# ADC_8CH.net
KiCad netlist of a schematic drawn in Altium Designer
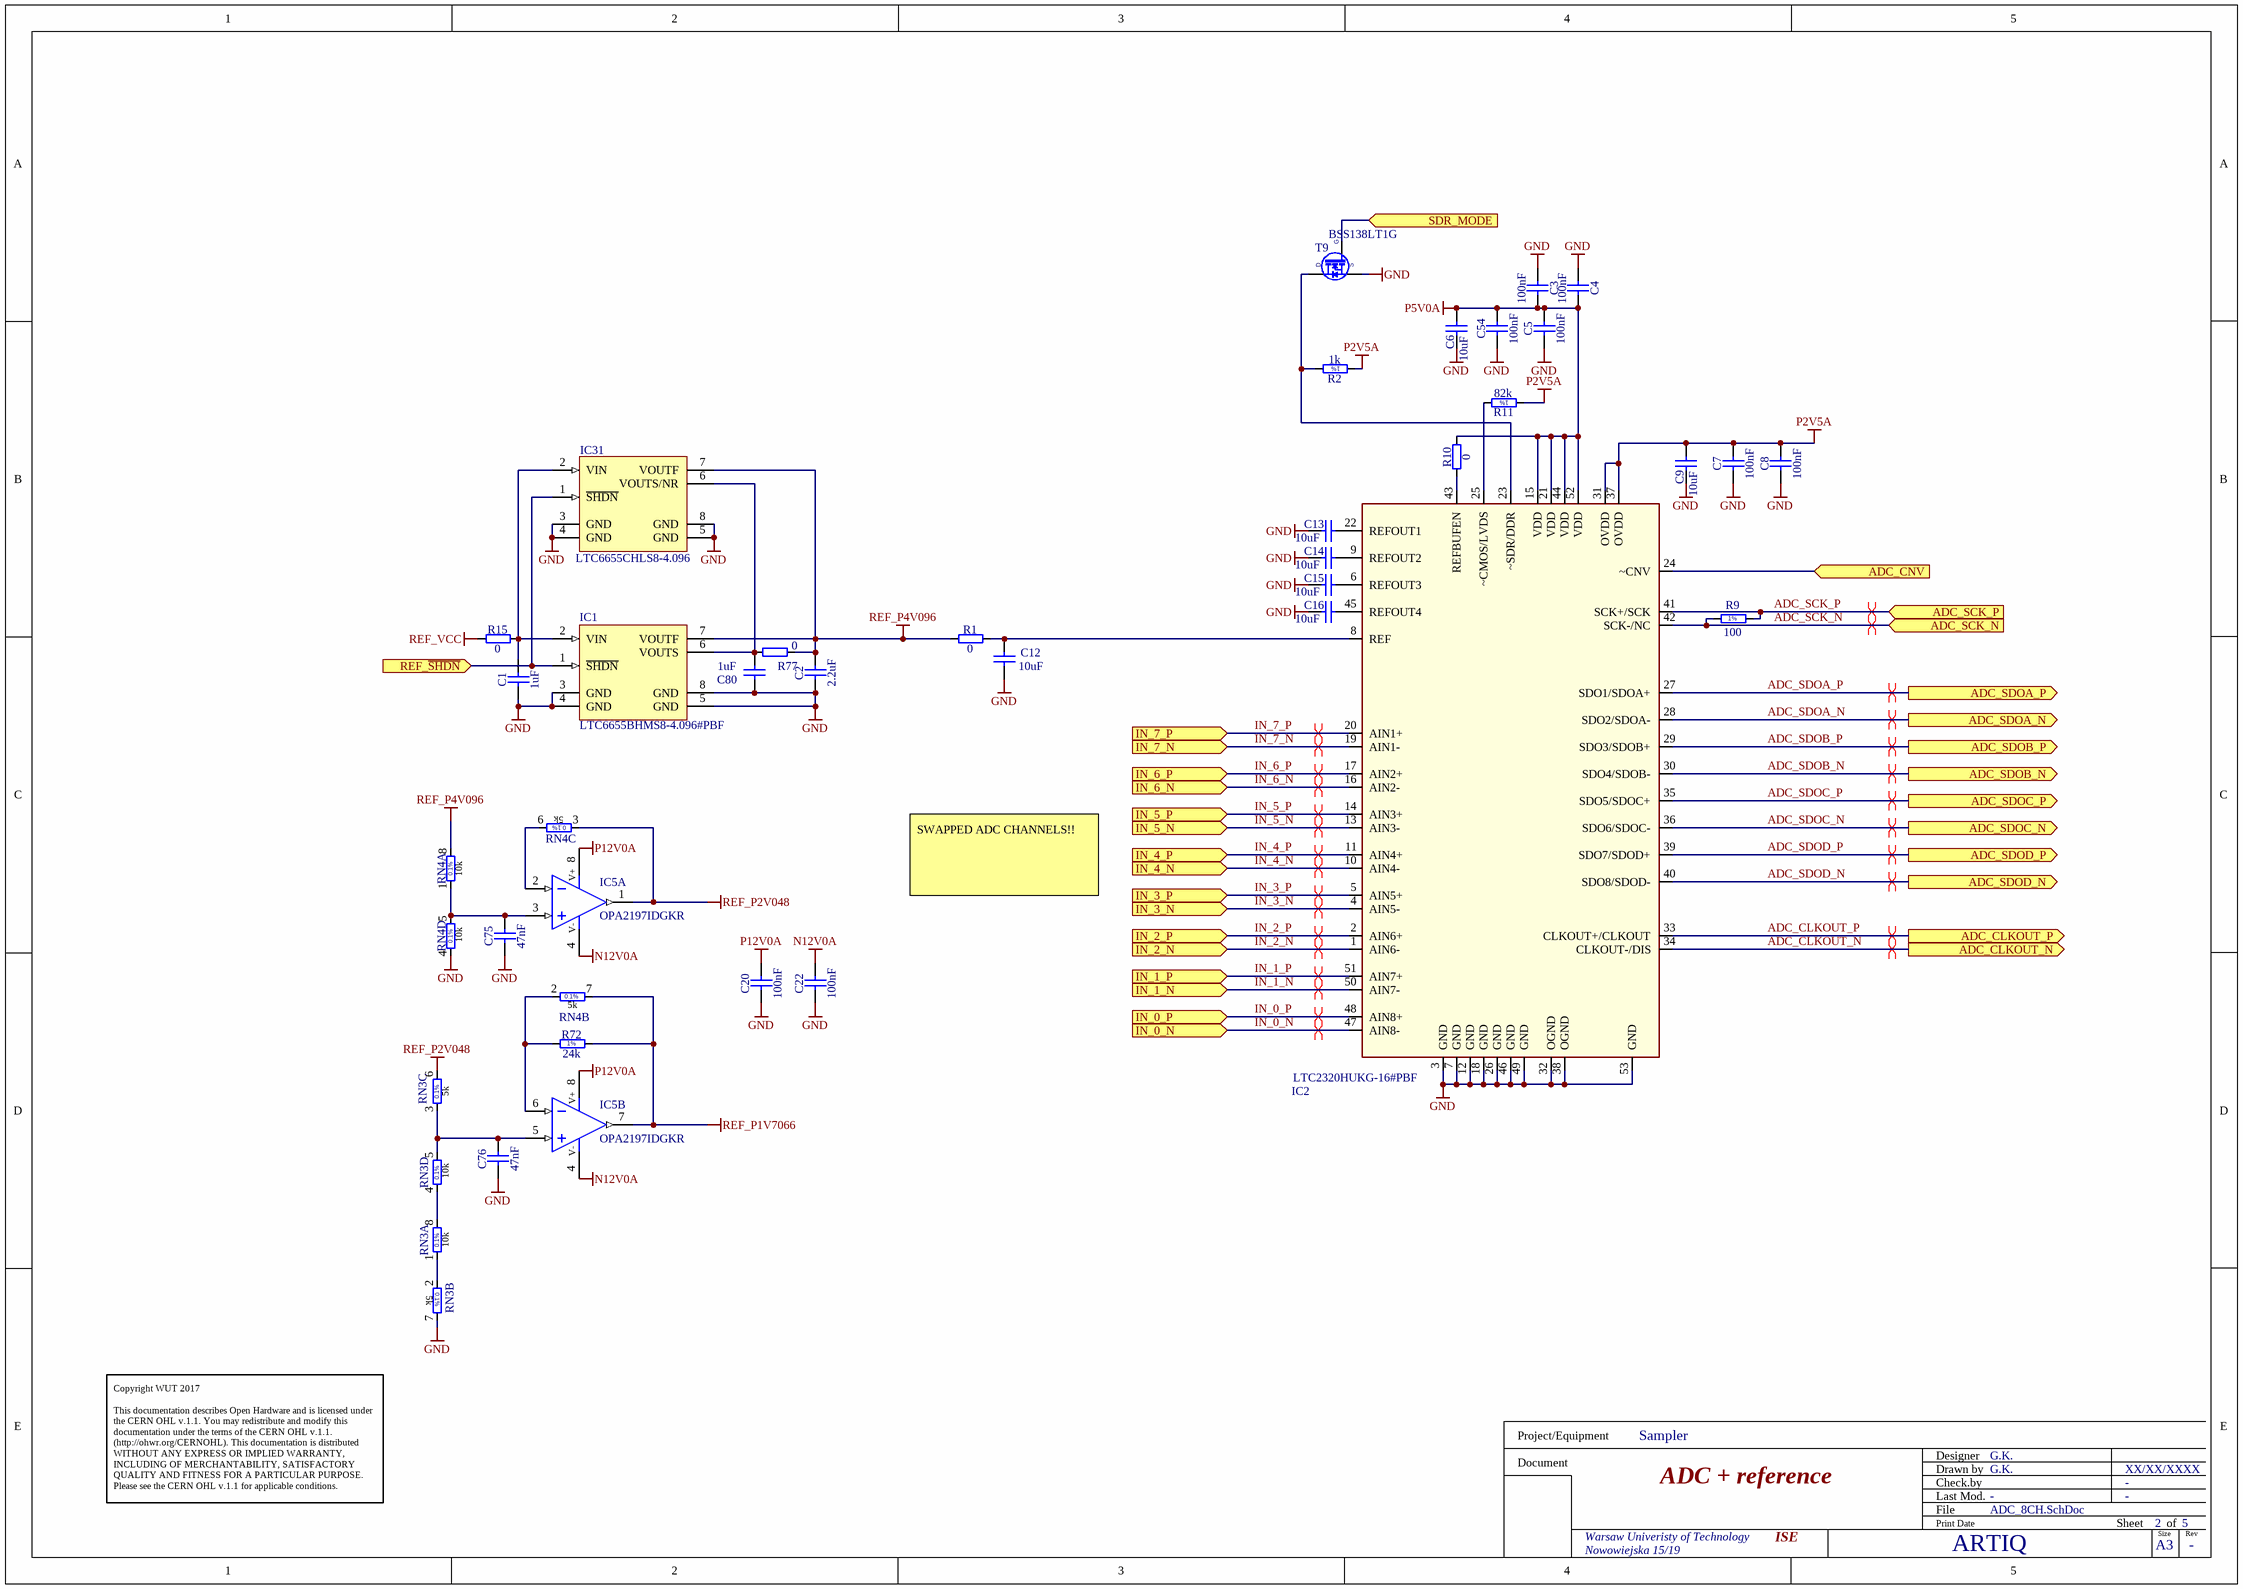
[diagram p0: ADC_8CH.SchDoc]

(export (version "E")
  (design (tool "Eeschema 10.0.6"))
  (components
    (comp (ref "C1")
      (value "1uF")
      (footprint "CAPC1608X87N")
      (description "Non-polarised capacitor")
      (fields
        (field (name "PART NUMBER") "CC0603_1UF_25V_10%_X7R")
        (field (name "VOLTAGE") "25V")
        (field (name "AUTHOR") "CERN DEM JLC")
      )
      (libsource (lib "Capacitors") (part "Capacitor - non polarized"))
    )
    (comp (ref "C2")
      (value "2.2uF")
      (footprint "CAPC1608X87N")
      (description "Non-polarised capacitor")
      (fields
        (field (name "PART NUMBER") "CC0603_2.2UF_16V_10%_X5R")
        (field (name "VOLTAGE") "16V")
        (field (name "AUTHOR") "CERN DEM JLC")
      )
      (libsource (lib "Capacitors") (part "Capacitor - non polarized"))
    )
    (comp (ref "C3")
      (value "100nF")
      (footprint "CAPC1608X87N")
      (description "Non-polarised capacitor")
      (fields
        (field (name "PART NUMBER") "CC0603_100NF_50V_10%_X7R")
        (field (name "VOLTAGE") "50V")
        (field (name "AUTHOR") "CERN DEM JLC")
      )
      (libsource (lib "Capacitors") (part "Capacitor - non polarized"))
    )
    (comp (ref "C4")
      (value "100nF")
      (footprint "CAPC1608X87N")
      (description "Non-polarised capacitor")
      (fields
        (field (name "PART NUMBER") "CC0603_100NF_50V_10%_X7R")
        (field (name "VOLTAGE") "50V")
        (field (name "AUTHOR") "CERN DEM JLC")
      )
      (libsource (lib "Capacitors") (part "Capacitor - non polarized"))
    )
    (comp (ref "C5")
      (value "100nF")
      (footprint "CAPC1608X87N")
      (description "Non-polarised capacitor")
      (fields
        (field (name "PART NUMBER") "CC0603_100NF_50V_10%_X7R")
        (field (name "VOLTAGE") "50V")
        (field (name "AUTHOR") "CERN DEM JLC")
      )
      (libsource (lib "Capacitors") (part "Capacitor - non polarized"))
    )
    (comp (ref "C6")
      (value "10uF")
      (footprint "CAPC2012X95N")
      (description "Non-polarised capacitor")
      (fields
        (field (name "PART NUMBER") "CC0805_10UF_25V_10%_X5R")
        (field (name "VOLTAGE") "25V")
        (field (name "AUTHOR") "CERN DEM JLC")
      )
      (libsource (lib "Capacitors") (part "Capacitor - non polarized"))
    )
    (comp (ref "C7")
      (value "100nF")
      (footprint "CAPC1608X87N")
      (description "Non-polarised capacitor")
      (fields
        (field (name "PART NUMBER") "CC0603_100NF_50V_10%_X7R")
        (field (name "VOLTAGE") "50V")
        (field (name "AUTHOR") "CERN DEM JLC")
      )
      (libsource (lib "Capacitors") (part "Capacitor - non polarized"))
    )
    (comp (ref "C8")
      (value "100nF")
      (footprint "CAPC1608X87N")
      (description "Non-polarised capacitor")
      (fields
        (field (name "PART NUMBER") "CC0603_100NF_50V_10%_X7R")
        (field (name "VOLTAGE") "50V")
        (field (name "AUTHOR") "CERN DEM JLC")
      )
      (libsource (lib "Capacitors") (part "Capacitor - non polarized"))
    )
    (comp (ref "C9")
      (value "10uF")
      (footprint "CAPC2012X95N")
      (description "Non-polarised capacitor")
      (fields
        (field (name "PART NUMBER") "CC0805_10UF_25V_10%_X5R")
        (field (name "VOLTAGE") "25V")
        (field (name "AUTHOR") "CERN DEM JLC")
      )
      (libsource (lib "Capacitors") (part "Capacitor - non polarized"))
    )
    (comp (ref "C12")
      (value "10uF")
      (footprint "CAPC2012X95N")
      (description "Non-polarised capacitor")
      (fields
        (field (name "PART NUMBER") "CC0805_10UF_25V_10%_X5R")
        (field (name "VOLTAGE") "25V")
        (field (name "AUTHOR") "CERN DEM JLC")
      )
      (libsource (lib "Capacitors") (part "Capacitor - non polarized"))
    )
    (comp (ref "C13")
      (value "10uF")
      (footprint "CAPC2012X95N")
      (description "Non-polarised capacitor")
      (fields
        (field (name "PART NUMBER") "CC0805_10UF_25V_10%_X5R")
        (field (name "VOLTAGE") "25V")
        (field (name "AUTHOR") "CERN DEM JLC")
      )
      (libsource (lib "Capacitors") (part "Capacitor - non polarized"))
    )
    (comp (ref "C14")
      (value "10uF")
      (footprint "CAPC2012X95N")
      (description "Non-polarised capacitor")
      (fields
        (field (name "PART NUMBER") "CC0805_10UF_25V_10%_X5R")
        (field (name "VOLTAGE") "25V")
        (field (name "AUTHOR") "CERN DEM JLC")
      )
      (libsource (lib "Capacitors") (part "Capacitor - non polarized"))
    )
    (comp (ref "C15")
      (value "10uF")
      (footprint "CAPC2012X95N")
      (description "Non-polarised capacitor")
      (fields
        (field (name "PART NUMBER") "CC0805_10UF_25V_10%_X5R")
        (field (name "VOLTAGE") "25V")
        (field (name "AUTHOR") "CERN DEM JLC")
      )
      (libsource (lib "Capacitors") (part "Capacitor - non polarized"))
    )
    (comp (ref "C16")
      (value "10uF")
      (footprint "CAPC2012X95N")
      (description "Non-polarised capacitor")
      (fields
        (field (name "PART NUMBER") "CC0805_10UF_25V_10%_X5R")
        (field (name "VOLTAGE") "25V")
        (field (name "AUTHOR") "CERN DEM JLC")
      )
      (libsource (lib "Capacitors") (part "Capacitor - non polarized"))
    )
    (comp (ref "C20")
      (value "100nF")
      (footprint "CAPC1005X55N")
      (description "Non-polarised capacitor")
      (fields
        (field (name "PART NUMBER") "CC0402_100NF_16V_10%_X5R")
        (field (name "VOLTAGE") "16V")
        (field (name "AUTHOR") "CERN DEM JLC")
      )
      (libsource (lib "Capacitors") (part "Capacitor - non polarized"))
    )
    (comp (ref "C22")
      (value "100nF")
      (footprint "CAPC1005X55N")
      (description "Non-polarised capacitor")
      (fields
        (field (name "PART NUMBER") "CC0402_100NF_16V_10%_X5R")
        (field (name "VOLTAGE") "16V")
        (field (name "AUTHOR") "CERN DEM JLC")
      )
      (libsource (lib "Capacitors") (part "Capacitor - non polarized"))
    )
    (comp (ref "C54")
      (value "100nF")
      (footprint "CAPC1608X87N")
      (description "Non-polarised capacitor")
      (fields
        (field (name "PART NUMBER") "CC0603_100NF_50V_10%_X7R")
        (field (name "VOLTAGE") "50V")
        (field (name "AUTHOR") "CERN DEM JLC")
      )
      (libsource (lib "Capacitors") (part "Capacitor - non polarized"))
    )
    (comp (ref "C75")
      (value "47nF")
      (footprint "CAPC2012X135N")
      (description "Non-polarised capacitor")
      (fields
        (field (name "PART NUMBER") "CC0805_47NF_25V_5%_C0G")
        (field (name "VOLTAGE") "25V")
        (field (name "AUTHOR") "CERN DEM JLC")
      )
      (libsource (lib "Capacitors") (part "Capacitor - non polarized"))
    )
    (comp (ref "C76")
      (value "47nF")
      (footprint "CAPC2012X135N")
      (description "Non-polarised capacitor")
      (fields
        (field (name "PART NUMBER") "CC0805_47NF_25V_5%_C0G")
        (field (name "VOLTAGE") "25V")
        (field (name "AUTHOR") "CERN DEM JLC")
      )
      (libsource (lib "Capacitors") (part "Capacitor - non polarized"))
    )
    (comp (ref "C80")
      (value "1uF")
      (footprint "CAPC1608X87N")
      (description "Non-polarised capacitor")
      (fields
        (field (name "PART NUMBER") "CC0603_1UF_25V_10%_X7R")
        (field (name "VOLTAGE") "25V")
        (field (name "AUTHOR") "CERN DEM JLC")
      )
      (libsource (lib "Capacitors") (part "Capacitor - non polarized"))
    )
    (comp (ref "IC1")
      (value "LTC6655BHMS8-4.096#PBF")
      (footprint "SOP65P490X110-8N")
      (description "0.25ppm Noise, Low Drift Precision Buffered Voltage Reference")
      (fields (field (name "MANUFACTURER") "LINEAR TECHNOLOGY") (field (name "AUTHOR") "GK"))
      (libsource (lib "LIBRARY_SCH") (part "REF_LTC6655"))
    )
    (comp (ref "IC2")
      (value "LTC2320HUKG-16#PBF")
      (footprint "QFN50P700X800X80_HS-53M")
      (description "Octal, 16-Bit, 1.5Msps/Ch  Simultaneous Sampling ADC")
      (fields (field (name "MANUFACTURER") "LINEAR TECHNOLOGY") (field (name "AUTHOR") "GK"))
      (libsource (lib "LIBRARY_SCH") (part "ADC_LTC2320HUKG-16"))
    )
    (comp (ref "IC5")
      (value "OPA2197IDGKR")
      (footprint "SOP65P490X110-8N")
      (description "36-V, Precision, Rail-to-Rail Input Output, Low Offset Voltage Op Amp 8-VSSOP")
      (fields (field (name "MANUFACTURER") "TEXAS INSTRUMENTS") (field (name "AUTHOR") "GK"))
      (libsource (lib "LIBRARY_SCH") (part "OA_OPA2197IDGKR"))
    )
    (comp (ref "IC31")
      (value "LTC6655CHLS8-4.096")
      (footprint "LCCS127P500X500X145-8N")
      (description "4.096, 1uA Precision Voltage Reference")
      (fields
        (field (name "PART NUMBER") "LTC6655CHLS8-4.096#PBF")
        (field (name "MANUFACTURER") "LINEAR TECHNOLOGY")
        (field (name "AUTHOR") "GK")
      )
      (libsource (lib "ICs_Analog_Interfaces") (part "REF_LTC6655CHLS8-4.096"))
    )
    (comp (ref "R1")
      (value "0")
      (footprint "RESC1005X40N")
      (description "Resistor")
      (fields
        (field (name "PART NUMBER") "R0402_0R_JUMPER")
        (field (name "MANUFACTURER") "GENERIC")
        (field (name "AUTHOR") "CERN DEM JLC")
      )
      (libsource (lib "Resistors") (part "Resistor"))
    )
    (comp (ref "R2")
      (value "1k")
      (footprint "RESC1608X55N")
      (description "Resistor - 1%")
      (fields
        (field (name "PART NUMBER") "R0603_1K_1%_0.1W_100PPM")
        (field (name "POWER") "0.1W")
        (field (name "AUTHOR") "CERN DEM JLC")
      )
      (libsource (lib "Resistors") (part "Resistor - 1%"))
    )
    (comp (ref "R9")
      (value "100")
      (footprint "RESC1005X40N")
      (description "Resistor - 1%")
      (fields
        (field (name "PART NUMBER") "R0402_100R_1%_0.1W_100PPM")
        (field (name "POWER") "0.1W")
        (field (name "AUTHOR") "CERN DEM JLC")
      )
      (libsource (lib "Resistors") (part "Resistor - 1%"))
    )
    (comp (ref "R10")
      (value "0")
      (footprint "RESC1005X40N")
      (description "Resistor")
      (fields
        (field (name "PART NUMBER") "R0402_0R_JUMPER")
        (field (name "MANUFACTURER") "GENERIC")
        (field (name "AUTHOR") "CERN DEM JLC")
      )
      (libsource (lib "Resistors") (part "Resistor"))
    )
    (comp (ref "R11")
      (value "82k")
      (footprint "RESC1608X55N")
      (description "Resistor - 1%")
      (fields
        (field (name "PART NUMBER") "R0603_82K_1%_0.1W_100PPM")
        (field (name "POWER") "0.1W")
        (field (name "AUTHOR") "CERN DEM JLC")
      )
      (libsource (lib "Resistors") (part "Resistor - 1%"))
    )
    (comp (ref "R15")
      (value "0")
      (footprint "RESC1005X40N")
      (description "Resistor")
      (fields
        (field (name "PART NUMBER") "R0402_0R_JUMPER")
        (field (name "MANUFACTURER") "GENERIC")
        (field (name "AUTHOR") "CERN DEM JLC")
      )
      (libsource (lib "Resistors") (part "Resistor"))
    )
    (comp (ref "R72")
      (value "24k")
      (footprint "RESC1608X55N")
      (description "Resistor - 1%")
      (fields
        (field (name "PART NUMBER") "R0603_24K_1%_0.1W_100PPM")
        (field (name "POWER") "0.1W")
        (field (name "AUTHOR") "CERN DEM JLC")
      )
      (libsource (lib "Resistors") (part "Resistor - 1%"))
    )
    (comp (ref "R77")
      (value "0")
      (footprint "RESC1005X40N")
      (description "Resistor")
      (fields
        (field (name "PART NUMBER") "R0402_0R_JUMPER")
        (field (name "MANUFACTURER") "GENERIC")
        (field (name "AUTHOR") "CERN DEM JLC")
      )
      (libsource (lib "Resistors") (part "Resistor"))
    )
    (comp (ref "RN3")
      (value "10k 5K 5K 10K")
      (footprint "SOIC127P600X175-8N")
      (description "DIL8 Resistor Network 4 Resistors 10k-5k-5k-10k 0.1%")
      (fields
        (field (name "PART NUMBER") "RN_10K_5K_VISHAY_AORN2-1AT3")
        (field (name "POWER") "4x0.1W")
        (field (name "AUTHOR") "CERN DEM JLC")
      )
      (libsource (lib "Resistors") (part "RN DIL8_4xR_10k-5k-5k-10k_0.1%"))
    )
    (comp (ref "RN4")
      (value "10k 5K 5K 10K")
      (footprint "SOIC127P600X175-8N")
      (description "DIL8 Resistor Network 4 Resistors 10k-5k-5k-10k 0.1%")
      (fields
        (field (name "PART NUMBER") "RN_10K_5K_VISHAY_AORN2-1AT3")
        (field (name "POWER") "4x0.1W")
        (field (name "AUTHOR") "CERN DEM JLC")
      )
      (libsource (lib "Resistors") (part "RN DIL8_4xR_10k-5k-5k-10k_0.1%"))
    )
    (comp (ref "T9")
      (value "BSS138LT1G")
      (footprint "SOT95P240X110-3N")
      (description "N-CHANNEL MOSFET WITH DIODE")
      (fields (field (name "MANUFACTURER") "ON SEMICONDUCTOR") (field (name "AUTHOR") "CERN DEM JLC"))
      (libsource (lib "ICs And Semiconductors") (part "N-MOSFET-D 1G 2S 3D"))
    )
  )
  (nets
    (net (code "1") (name "/ADC_CLKOUT_N") (class "Default")
      (node (ref "IC2") (pin "34") (pinfunction "CLKOUT-/DIS_34") (pintype "passive"))
    )
    (net (code "2") (name "/ADC_CLKOUT_P") (class "Default")
      (node (ref "IC2") (pin "33") (pinfunction "CLKOUT+/CLKOUT_33") (pintype "passive"))
    )
    (net (code "3") (name "/ADC_CNV") (class "Default")
      (node (ref "IC2") (pin "24") (pinfunction "~CNV_24") (pintype "passive"))
    )
    (net (code "4") (name "/ADC_SCK_N") (class "Default")
      (node (ref "IC2") (pin "42") (pinfunction "SCK-/NC_42") (pintype "passive"))
      (node (ref "R9") (pin "1") (pinfunction "1_1") (pintype "passive"))
    )
    (net (code "5") (name "/ADC_SCK_P") (class "Default")
      (node (ref "IC2") (pin "41") (pinfunction "SCK+/SCK_41") (pintype "passive"))
      (node (ref "R9") (pin "2") (pinfunction "2_2") (pintype "passive"))
    )
    (net (code "6") (name "/ADC_SDOA_N") (class "Default")
      (node (ref "IC2") (pin "28") (pinfunction "SDO2/SDOA-_28") (pintype "passive"))
    )
    (net (code "7") (name "/ADC_SDOA_P") (class "Default")
      (node (ref "IC2") (pin "27") (pinfunction "SDO1/SDOA+_27") (pintype "passive"))
    )
    (net (code "8") (name "/ADC_SDOB_N") (class "Default")
      (node (ref "IC2") (pin "30") (pinfunction "SDO4/SDOB-_30") (pintype "passive"))
    )
    (net (code "9") (name "/ADC_SDOB_P") (class "Default")
      (node (ref "IC2") (pin "29") (pinfunction "SDO3/SDOB+_29") (pintype "passive"))
    )
    (net (code "10") (name "/ADC_SDOC_N") (class "Default")
      (node (ref "IC2") (pin "36") (pinfunction "SDO6/SDOC-_36") (pintype "passive"))
    )
    (net (code "11") (name "/ADC_SDOC_P") (class "Default")
      (node (ref "IC2") (pin "35") (pinfunction "SDO5/SDOC+_35") (pintype "passive"))
    )
    (net (code "12") (name "/ADC_SDOD_N") (class "Default")
      (node (ref "IC2") (pin "40") (pinfunction "SDO8/SDOD-_40") (pintype "passive"))
    )
    (net (code "13") (name "/ADC_SDOD_P") (class "Default")
      (node (ref "IC2") (pin "39") (pinfunction "SDO7/SDOD+_39") (pintype "passive"))
    )
    (net (code "14") (name "/IN_0_N") (class "Default")
      (node (ref "IC2") (pin "47") (pinfunction "AIN8-_47") (pintype "passive"))
    )
    (net (code "15") (name "/IN_0_P") (class "Default")
      (node (ref "IC2") (pin "48") (pinfunction "AIN8+_48") (pintype "passive"))
    )
    (net (code "16") (name "/IN_1_N") (class "Default")
      (node (ref "IC2") (pin "50") (pinfunction "AIN7-_50") (pintype "passive"))
    )
    (net (code "17") (name "/IN_1_P") (class "Default")
      (node (ref "IC2") (pin "51") (pinfunction "AIN7+_51") (pintype "passive"))
    )
    (net (code "18") (name "/IN_2_N") (class "Default")
      (node (ref "IC2") (pin "1") (pinfunction "AIN6-_1") (pintype "passive"))
    )
    (net (code "19") (name "/IN_2_P") (class "Default")
      (node (ref "IC2") (pin "2") (pinfunction "AIN6+_2") (pintype "passive"))
    )
    (net (code "20") (name "/IN_3_N") (class "Default")
      (node (ref "IC2") (pin "4") (pinfunction "AIN5-_4") (pintype "passive"))
    )
    (net (code "21") (name "/IN_3_P") (class "Default")
      (node (ref "IC2") (pin "5") (pinfunction "AIN5+_5") (pintype "passive"))
    )
    (net (code "22") (name "/IN_4_N") (class "Default")
      (node (ref "IC2") (pin "10") (pinfunction "AIN4-_10") (pintype "passive"))
    )
    (net (code "23") (name "/IN_4_P") (class "Default")
      (node (ref "IC2") (pin "11") (pinfunction "AIN4+_11") (pintype "passive"))
    )
    (net (code "24") (name "/IN_5_N") (class "Default")
      (node (ref "IC2") (pin "13") (pinfunction "AIN3-_13") (pintype "passive"))
    )
    (net (code "25") (name "/IN_5_P") (class "Default")
      (node (ref "IC2") (pin "14") (pinfunction "AIN3+_14") (pintype "passive"))
    )
    (net (code "26") (name "/IN_6_N") (class "Default")
      (node (ref "IC2") (pin "16") (pinfunction "AIN2-_16") (pintype "passive"))
    )
    (net (code "27") (name "/IN_6_P") (class "Default")
      (node (ref "IC2") (pin "17") (pinfunction "AIN2+_17") (pintype "passive"))
    )
    (net (code "28") (name "/IN_7_N") (class "Default")
      (node (ref "IC2") (pin "19") (pinfunction "AIN1-_19") (pintype "passive"))
    )
    (net (code "29") (name "/IN_7_P") (class "Default")
      (node (ref "IC2") (pin "20") (pinfunction "AIN1+_20") (pintype "passive"))
    )
    (net (code "30") (name "/REF_~{SHDN}") (class "Default")
      (node (ref "IC1") (pin "1") (pinfunction "~{SHDN}_1") (pintype "input"))
      (node (ref "IC31") (pin "1") (pinfunction "~{SHDN}_1") (pintype "input"))
    )
    (net (code "31") (name "/SDR_MODE") (class "Default")
      (node (ref "T9") (pin "1") (pinfunction "G_1") (pintype "passive"))
    )
    (net (code "32") (name "GND") (class "Default")
      (node (ref "C1") (pin "1") (pinfunction "1_1") (pintype "passive"))
      (node (ref "C12") (pin "1") (pinfunction "1_1") (pintype "passive"))
      (node (ref "C13") (pin "1") (pinfunction "1_1") (pintype "passive"))
      (node (ref "C14") (pin "1") (pinfunction "1_1") (pintype "passive"))
      (node (ref "C15") (pin "1") (pinfunction "1_1") (pintype "passive"))
      (node (ref "C16") (pin "1") (pinfunction "1_1") (pintype "passive"))
      (node (ref "C2") (pin "1") (pinfunction "1_1") (pintype "passive"))
      (node (ref "C20") (pin "1") (pinfunction "1_1") (pintype "passive"))
      (node (ref "C22") (pin "1") (pinfunction "1_1") (pintype "passive"))
      (node (ref "C3") (pin "1") (pinfunction "1_1") (pintype "passive"))
      (node (ref "C4") (pin "1") (pinfunction "1_1") (pintype "passive"))
      (node (ref "C5") (pin "1") (pinfunction "1_1") (pintype "passive"))
      (node (ref "C54") (pin "1") (pinfunction "1_1") (pintype "passive"))
      (node (ref "C6") (pin "1") (pinfunction "1_1") (pintype "passive"))
      (node (ref "C7") (pin "1") (pinfunction "1_1") (pintype "passive"))
      (node (ref "C75") (pin "1") (pinfunction "1_1") (pintype "passive"))
      (node (ref "C76") (pin "1") (pinfunction "1_1") (pintype "passive"))
      (node (ref "C8") (pin "1") (pinfunction "1_1") (pintype "passive"))
      (node (ref "C80") (pin "1") (pinfunction "1_1") (pintype "passive"))
      (node (ref "C9") (pin "1") (pinfunction "1_1") (pintype "passive"))
      (node (ref "IC1") (pin "3") (pinfunction "GND_3") (pintype "power_in"))
      (node (ref "IC1") (pin "4") (pinfunction "GND_4") (pintype "power_in"))
      (node (ref "IC1") (pin "5") (pinfunction "GND_5") (pintype "power_in"))
      (node (ref "IC1") (pin "8") (pinfunction "GND_8") (pintype "power_in"))
      (node (ref "IC2") (pin "12") (pinfunction "GND_12") (pintype "passive"))
      (node (ref "IC2") (pin "18") (pinfunction "GND_18") (pintype "passive"))
      (node (ref "IC2") (pin "26") (pinfunction "GND_26") (pintype "passive"))
      (node (ref "IC2") (pin "3") (pinfunction "GND_3") (pintype "passive"))
      (node (ref "IC2") (pin "32") (pinfunction "OGND_32") (pintype "passive"))
      (node (ref "IC2") (pin "38") (pinfunction "OGND_38") (pintype "passive"))
      (node (ref "IC2") (pin "46") (pinfunction "GND_46") (pintype "passive"))
      (node (ref "IC2") (pin "49") (pinfunction "GND_49") (pintype "passive"))
      (node (ref "IC2") (pin "53") (pinfunction "GND_53") (pintype "passive"))
      (node (ref "IC2") (pin "7") (pinfunction "GND_7") (pintype "passive"))
      (node (ref "IC31") (pin "3") (pinfunction "GND_3") (pintype "power_in"))
      (node (ref "IC31") (pin "4") (pinfunction "GND_4") (pintype "power_in"))
      (node (ref "IC31") (pin "5") (pinfunction "GND_5") (pintype "power_in"))
      (node (ref "IC31") (pin "8") (pinfunction "GND_8") (pintype "power_in"))
      (node (ref "RN3") (pin "7") (pinfunction "7_7") (pintype "passive"))
      (node (ref "RN4") (pin "4") (pinfunction "4_4") (pintype "passive"))
      (node (ref "T9") (pin "2") (pinfunction "S_2") (pintype "passive"))
    )
    (net (code "33") (name "N12V0A") (class "Default")
      (node (ref "C22") (pin "2") (pinfunction "2_2") (pintype "passive"))
      (node (ref "IC5") (pin "4") (pinfunction "V-_4") (pintype "power_in"))
    )
    (net (code "34") (name "Net-(IC1-VIN)") (class "Default")
      (node (ref "C1") (pin "2") (pinfunction "2_2") (pintype "passive"))
      (node (ref "IC1") (pin "2") (pinfunction "VIN_2") (pintype "input"))
      (node (ref "IC31") (pin "2") (pinfunction "VIN_2") (pintype "input"))
      (node (ref "R15") (pin "2") (pinfunction "2_2") (pintype "passive"))
    )
    (net (code "35") (name "Net-(IC1-VOUTS)") (class "Default")
      (node (ref "C80") (pin "2") (pinfunction "2_2") (pintype "passive"))
      (node (ref "IC1") (pin "6") (pinfunction "VOUTS_6") (pintype "power_in"))
      (node (ref "IC31") (pin "6") (pinfunction "VOUTS/NR_6") (pintype "power_in"))
      (node (ref "R77") (pin "1") (pinfunction "1_1") (pintype "passive"))
    )
    (net (code "36") (name "Net-(IC2-REF)") (class "Default")
      (node (ref "C12") (pin "2") (pinfunction "2_2") (pintype "passive"))
      (node (ref "IC2") (pin "8") (pinfunction "REF_8") (pintype "passive"))
      (node (ref "R1") (pin "2") (pinfunction "2_2") (pintype "passive"))
    )
    (net (code "37") (name "Net-(IC2-REFBUFEN)") (class "Default")
      (node (ref "IC2") (pin "43") (pinfunction "REFBUFEN_43") (pintype "passive"))
      (node (ref "R10") (pin "1") (pinfunction "1_1") (pintype "passive"))
    )
    (net (code "38") (name "Net-(IC2-REFOUT1)") (class "Default")
      (node (ref "C13") (pin "2") (pinfunction "2_2") (pintype "passive"))
      (node (ref "IC2") (pin "22") (pinfunction "REFOUT1_22") (pintype "passive"))
    )
    (net (code "39") (name "Net-(IC2-REFOUT2)") (class "Default")
      (node (ref "C14") (pin "2") (pinfunction "2_2") (pintype "passive"))
      (node (ref "IC2") (pin "9") (pinfunction "REFOUT2_9") (pintype "passive"))
    )
    (net (code "40") (name "Net-(IC2-REFOUT3)") (class "Default")
      (node (ref "C15") (pin "2") (pinfunction "2_2") (pintype "passive"))
      (node (ref "IC2") (pin "6") (pinfunction "REFOUT3_6") (pintype "passive"))
    )
    (net (code "41") (name "Net-(IC2-REFOUT4)") (class "Default")
      (node (ref "C16") (pin "2") (pinfunction "2_2") (pintype "passive"))
      (node (ref "IC2") (pin "45") (pinfunction "REFOUT4_45") (pintype "passive"))
    )
    (net (code "42") (name "Net-(IC2-~CMOS{slash}LVDS)") (class "Default")
      (node (ref "IC2") (pin "25") (pinfunction "~CMOS/LVDS_25") (pintype "passive"))
      (node (ref "R11") (pin "2") (pinfunction "2_2") (pintype "passive"))
    )
    (net (code "43") (name "Net-(IC2-~SDR{slash}DDR)") (class "Default")
      (node (ref "IC2") (pin "23") (pinfunction "~SDR/DDR_23") (pintype "passive"))
      (node (ref "R2") (pin "2") (pinfunction "2_2") (pintype "passive"))
      (node (ref "T9") (pin "3") (pinfunction "D_3") (pintype "passive"))
    )
    (net (code "44") (name "Net-(IC5A-IN+)") (class "Default")
      (node (ref "C75") (pin "2") (pinfunction "2_2") (pintype "passive"))
      (node (ref "IC5") (pin "3") (pinfunction "IN+_3") (pintype "input"))
      (node (ref "RN4") (pin "1") (pinfunction "1_1") (pintype "passive"))
      (node (ref "RN4") (pin "5") (pinfunction "5_5") (pintype "passive"))
    )
    (net (code "45") (name "Net-(IC5A-IN-)") (class "Default")
      (node (ref "IC5") (pin "2") (pinfunction "IN-_2") (pintype "input"))
      (node (ref "RN4") (pin "6") (pinfunction "6_6") (pintype "passive"))
    )
    (net (code "46") (name "Net-(IC5B-IN+)") (class "Default")
      (node (ref "C76") (pin "2") (pinfunction "2_2") (pintype "passive"))
      (node (ref "IC5") (pin "5") (pinfunction "IN+_5") (pintype "input"))
      (node (ref "RN3") (pin "3") (pinfunction "3_3") (pintype "passive"))
      (node (ref "RN3") (pin "5") (pinfunction "5_5") (pintype "passive"))
    )
    (net (code "47") (name "Net-(IC5B-IN-)") (class "Default")
      (node (ref "IC5") (pin "6") (pinfunction "IN-_6") (pintype "input"))
      (node (ref "R72") (pin "1") (pinfunction "1_1") (pintype "passive"))
      (node (ref "RN4") (pin "2") (pinfunction "2_2") (pintype "passive"))
    )
    (net (code "48") (name "Net-(RN3-Pad1)") (class "Default")
      (node (ref "RN3") (pin "1") (pinfunction "1_1") (pintype "passive"))
      (node (ref "RN3") (pin "2") (pinfunction "2_2") (pintype "passive"))
    )
    (net (code "49") (name "Net-(RN3-Pad4)") (class "Default")
      (node (ref "RN3") (pin "4") (pinfunction "4_4") (pintype "passive"))
      (node (ref "RN3") (pin "8") (pinfunction "8_8") (pintype "passive"))
    )
    (net (code "50") (name "P2V5A") (class "Default")
      (node (ref "C7") (pin "2") (pinfunction "2_2") (pintype "passive"))
      (node (ref "C8") (pin "2") (pinfunction "2_2") (pintype "passive"))
      (node (ref "C9") (pin "2") (pinfunction "2_2") (pintype "passive"))
      (node (ref "IC2") (pin "31") (pinfunction "OVDD_31") (pintype "passive"))
      (node (ref "IC2") (pin "37") (pinfunction "OVDD_37") (pintype "passive"))
      (node (ref "R11") (pin "1") (pinfunction "1_1") (pintype "passive"))
      (node (ref "R2") (pin "1") (pinfunction "1_1") (pintype "passive"))
    )
    (net (code "51") (name "P5V0A") (class "Default")
      (node (ref "C3") (pin "2") (pinfunction "2_2") (pintype "passive"))
      (node (ref "C4") (pin "2") (pinfunction "2_2") (pintype "passive"))
      (node (ref "C5") (pin "2") (pinfunction "2_2") (pintype "passive"))
      (node (ref "C54") (pin "2") (pinfunction "2_2") (pintype "passive"))
      (node (ref "C6") (pin "2") (pinfunction "2_2") (pintype "passive"))
      (node (ref "IC2") (pin "15") (pinfunction "VDD_15") (pintype "passive"))
      (node (ref "IC2") (pin "21") (pinfunction "VDD_21") (pintype "passive"))
      (node (ref "IC2") (pin "44") (pinfunction "VDD_44") (pintype "passive"))
      (node (ref "IC2") (pin "52") (pinfunction "VDD_52") (pintype "passive"))
      (node (ref "R10") (pin "2") (pinfunction "2_2") (pintype "passive"))
    )
    (net (code "52") (name "P12V0A") (class "Default")
      (node (ref "C20") (pin "2") (pinfunction "2_2") (pintype "passive"))
      (node (ref "IC5") (pin "8") (pinfunction "V+_8") (pintype "power_in"))
    )
    (net (code "53") (name "REF_P1V7066") (class "Default")
      (node (ref "IC5") (pin "7") (pinfunction "OUT_7") (pintype "output"))
      (node (ref "R72") (pin "2") (pinfunction "2_2") (pintype "passive"))
      (node (ref "RN4") (pin "7") (pinfunction "7_7") (pintype "passive"))
    )
    (net (code "54") (name "REF_P2V048") (class "Default")
      (node (ref "IC5") (pin "1") (pinfunction "OUT_1") (pintype "output"))
      (node (ref "RN3") (pin "6") (pinfunction "6_6") (pintype "passive"))
      (node (ref "RN4") (pin "3") (pinfunction "3_3") (pintype "passive"))
    )
    (net (code "55") (name "REF_P4V096") (class "Default")
      (node (ref "C2") (pin "2") (pinfunction "2_2") (pintype "passive"))
      (node (ref "IC1") (pin "7") (pinfunction "VOUTF_7") (pintype "power_in"))
      (node (ref "IC31") (pin "7") (pinfunction "VOUTF_7") (pintype "power_in"))
      (node (ref "R1") (pin "1") (pinfunction "1_1") (pintype "passive"))
      (node (ref "R77") (pin "2") (pinfunction "2_2") (pintype "passive"))
      (node (ref "RN4") (pin "8") (pinfunction "8_8") (pintype "passive"))
    )
    (net (code "56") (name "REF_VCC") (class "Default")
      (node (ref "R15") (pin "1") (pinfunction "1_1") (pintype "passive"))
    )
  )
)
